# Sheet-BATTERY-V2_1.net
KiCad netlist of a schematic drawn in Altium Designer
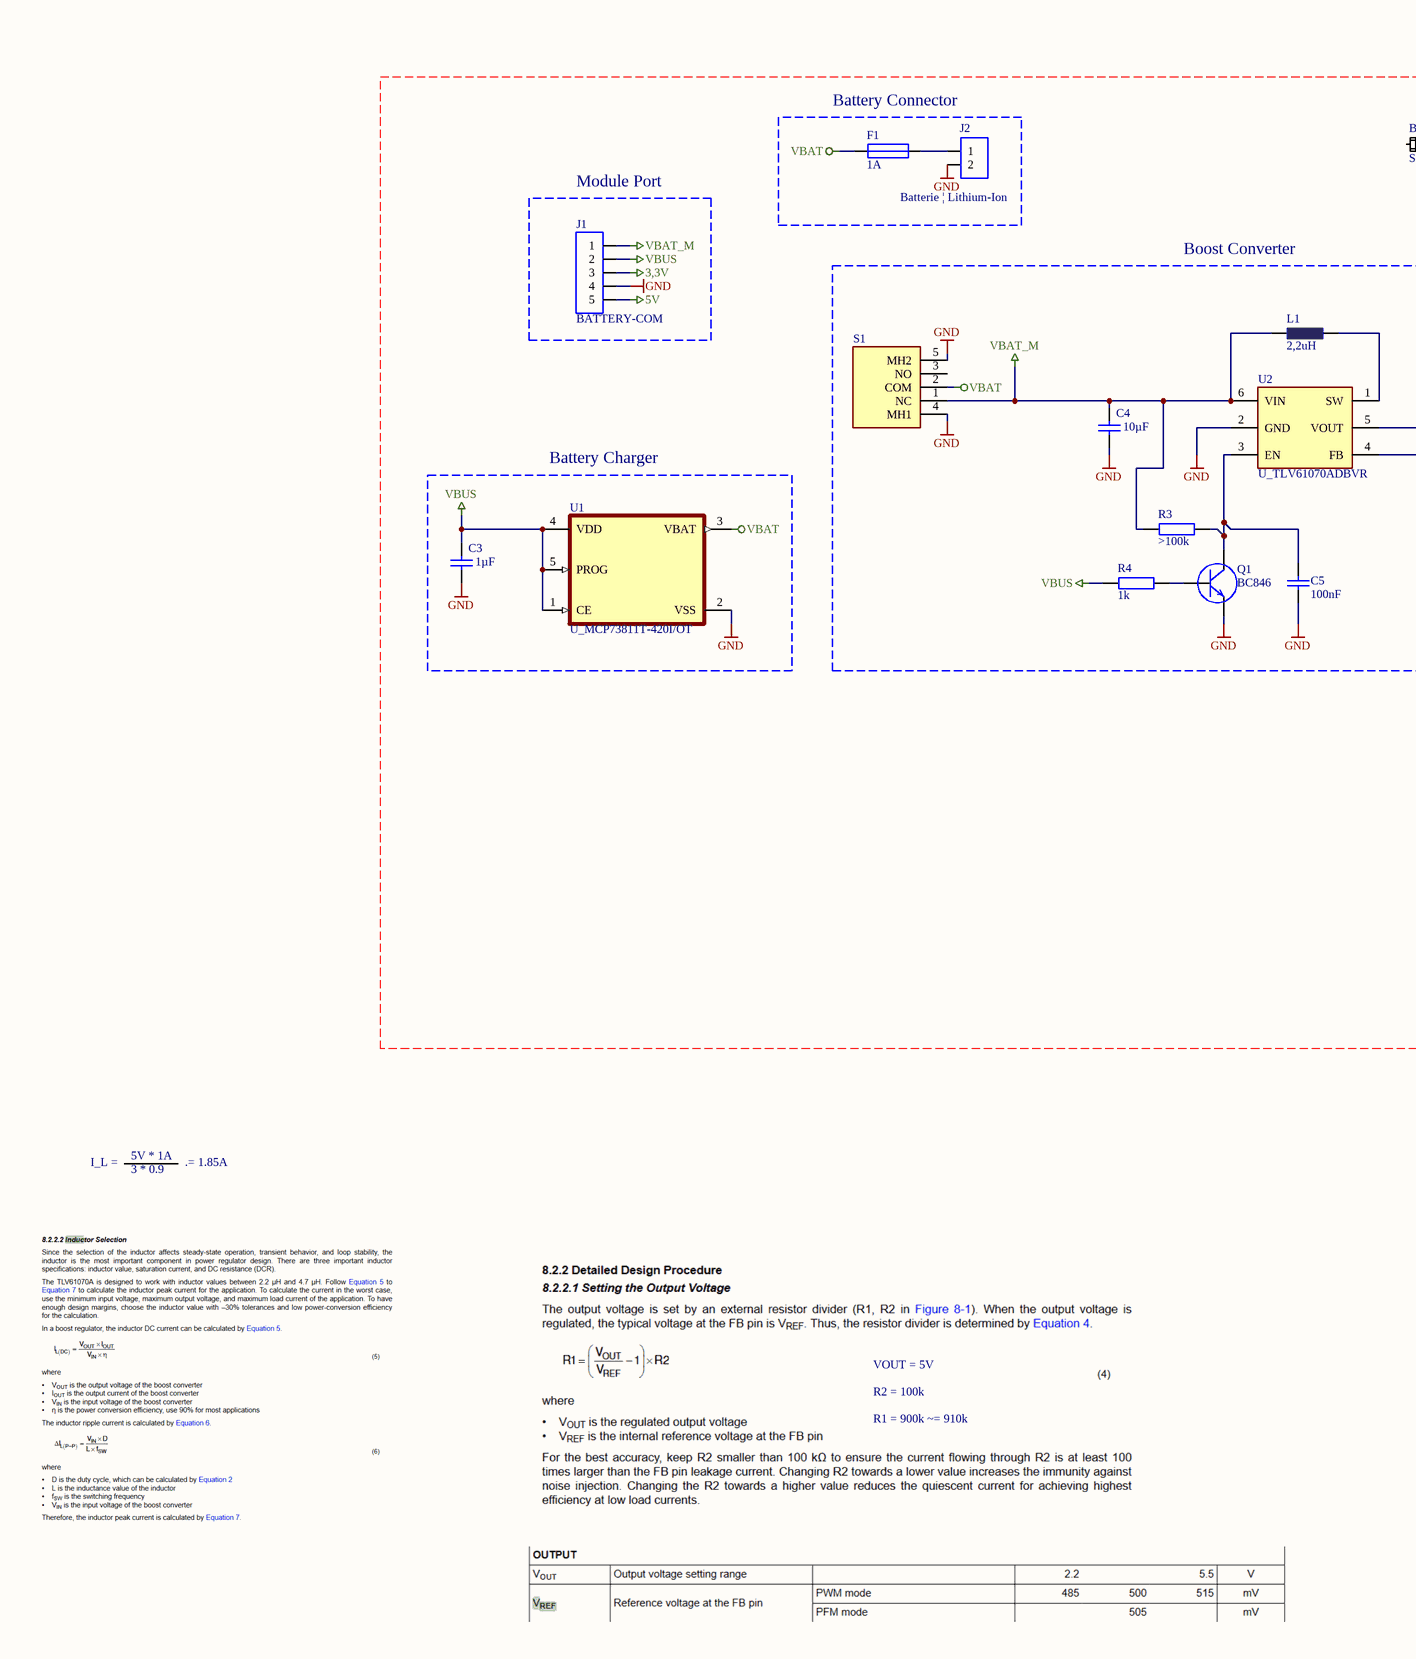
[diagram p0: Sheet-BATTERY-V2.1.SchDoc, left]
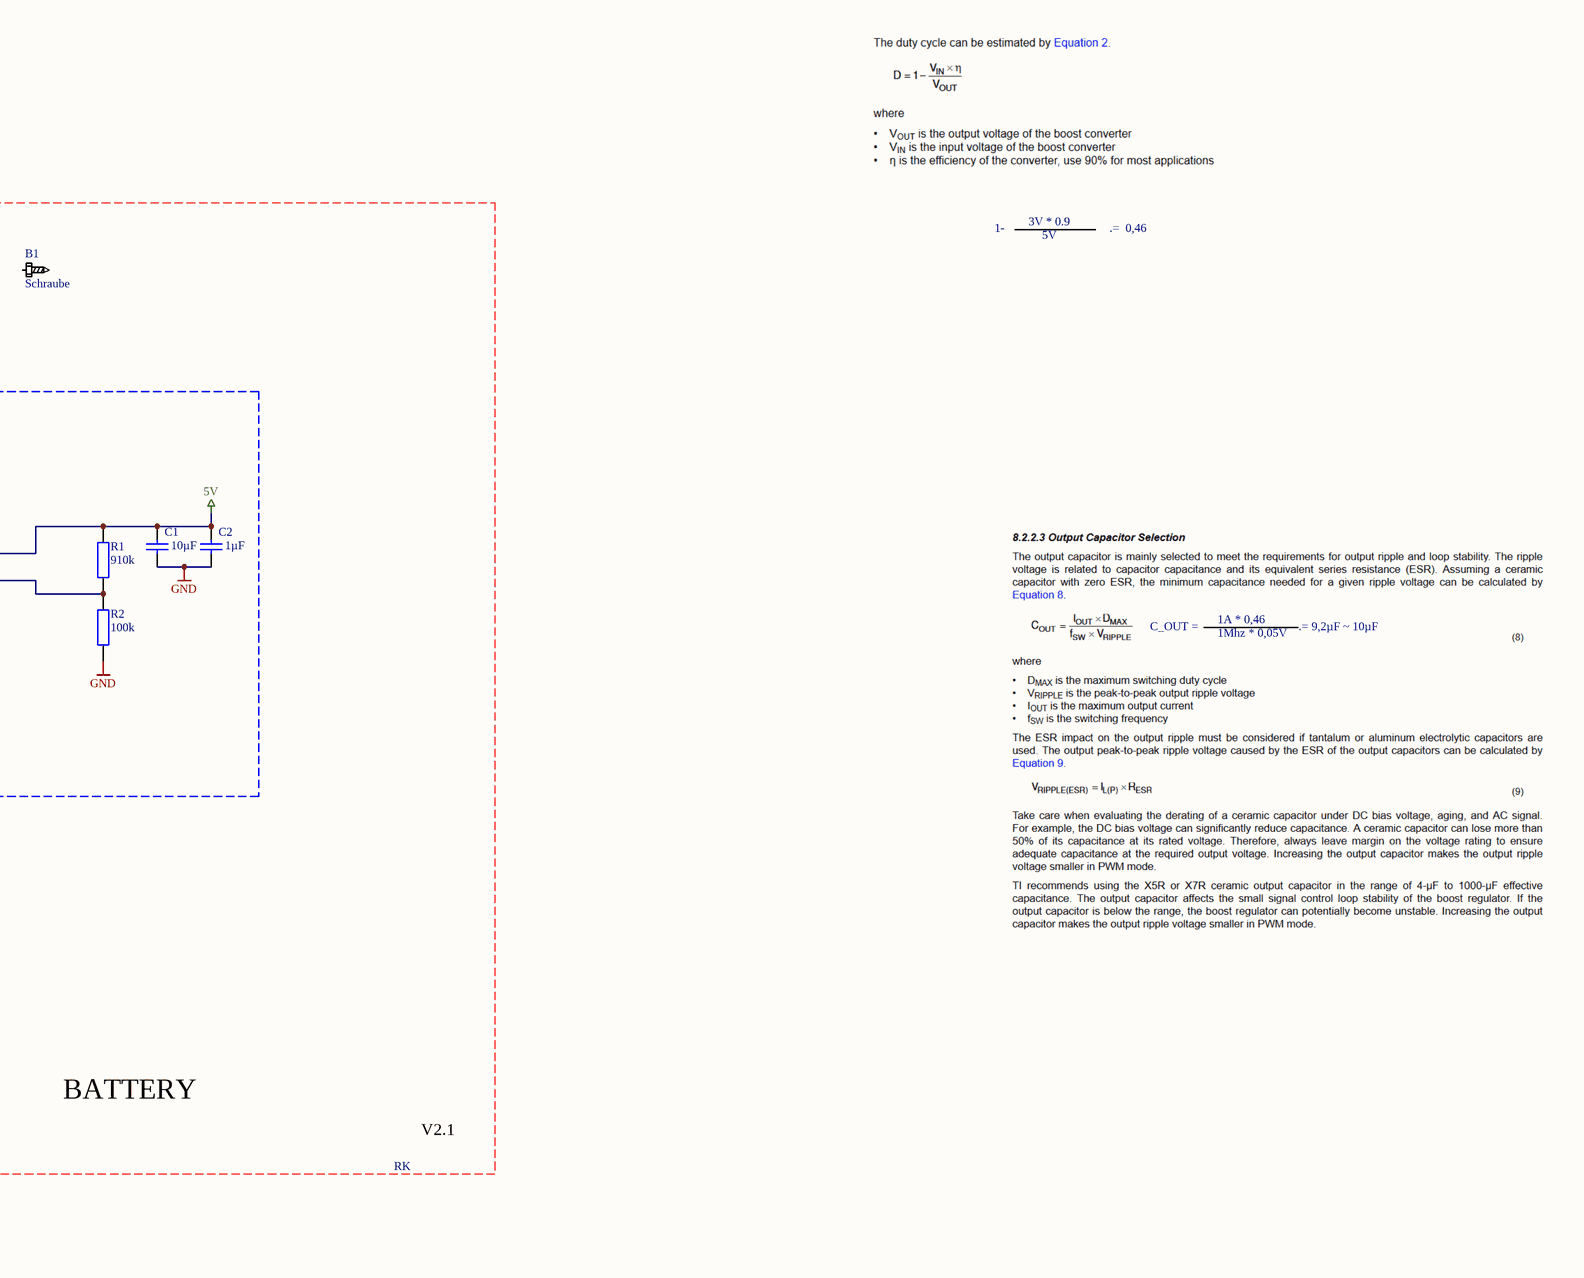
[diagram p1: Sheet-BATTERY-V2.1.SchDoc, right]

(export (version "E")
  (design (tool "Eeschema 10.0.6"))
  (components
    (comp (ref "B1")
      (value "Schraube")
      (footprint "B_Schraube-M3 PAD")
      (description "Schraubenloch für M3 Schrauben")
      (libsource (lib "SCHLIB-PCSB_5.1.3") (part "B_Schraube"))
    )
    (comp (ref "C1")
      (value "10µF")
      (footprint "C_SMD_0805")
      (description "Kondensator SMD Universal, Keramik, Folie, usw.")
      (libsource (lib "SCHLIB-PCSB_5.1.3") (part "C_SMD_KO"))
    )
    (comp (ref "C2")
      (value "1µF")
      (footprint "C_SMD_0603")
      (description "Kondensator SMD Universal, Keramik, Folie, usw.")
      (libsource (lib "SCHLIB-PCSB_5.1.3") (part "C_SMD_KO"))
    )
    (comp (ref "C3")
      (value "1µF")
      (footprint "C_SMD_0603")
      (description "Kondensator SMD Universal, Keramik, Folie, usw.")
      (libsource (lib "SCHLIB-PCSB_5.1.3") (part "C_SMD_KO"))
    )
    (comp (ref "C4")
      (value "10µF")
      (footprint "C_SMD_0805")
      (description "Kondensator SMD Universal, Keramik, Folie, usw.")
      (libsource (lib "SCHLIB-PCSB_5.1.3") (part "C_SMD_KO"))
    )
    (comp (ref "C5")
      (value "100nF")
      (footprint "C_SMD_0603")
      (description "Kondensator SMD Universal, Keramik, Folie, usw.")
      (libsource (lib "SCHLIB-PCSB_5.1.3") (part "C_SMD_KO"))
    )
    (comp (ref "F1")
      (value "1A")
      (footprint "F_OMF63_Schurtner")
      (description "Sicherung")
      (libsource (lib "SCHLIB-PCSB_5.1.3") (part "F_THT_Fuse"))
    )
    (comp (ref "J1")
      (value "BATTERY-COM")
      (footprint "SIP-5")
      (description "Stecker")
      (libsource (lib "SCHLIB-PCSB_5.1.3") (part "J_THT_CON5"))
    )
    (comp (ref "J2")
      (value "Batterie ¦ Lithium-Ion")
      (footprint "J_THT_Printklemme 2x")
      (description "Stecker")
      (libsource (lib "SCHLIB-PCSB_5.1.3") (part "J_THT_CON2"))
    )
    (comp (ref "L1")
      (value "2,2uH")
      (footprint "L_SMD_74438357100")
      (description "Spule SMD")
      (libsource (lib "SCHLIB-PCSB_5.1.3") (part "L_SMD_Spule"))
    )
    (comp (ref "Q1")
      (value "BC846")
      (footprint "SOT-23-3_BC846")
      (description "NPN Transistor")
      (libsource (lib "SCHLIB-PCSB_5.1.3") (part "Q_SMD_NPN"))
    )
    (comp (ref "R1")
      (value "910k")
      (footprint "R_SMD_0805")
      (description "Widerstand SMD")
      (libsource (lib "SCHLIB-PCSB_5.1.3") (part "R_SMD_Widerstand"))
    )
    (comp (ref "R2")
      (value "100k")
      (footprint "R_SMD_0805")
      (description "Widerstand SMD")
      (libsource (lib "SCHLIB-PCSB_5.1.3") (part "R_SMD_Widerstand"))
    )
    (comp (ref "R3")
      (value ">100k")
      (footprint "R_SMD_0603")
      (description "Widerstand SMD")
      (libsource (lib "SCHLIB-PCSB_5.1.3") (part "R_SMD_Widerstand"))
    )
    (comp (ref "R4")
      (value "1k")
      (footprint "R_SMD_0603")
      (description "Widerstand SMD")
      (libsource (lib "SCHLIB-PCSB_5.1.3") (part "R_SMD_Widerstand"))
    )
    (comp (ref "S1")
      (value "S_SLW-1298856-5A-RA-N-D")
      (footprint "SLW12988565ARAND")
      (description "Switch")
      (fields (field (name "MANUFACTURER_PART_NUMBER") "SLW-1298856-5A-RA-N-D"))
      (libsource (lib "SCHLIB-PCSB_5.1.3") (part "S_SLW-1298856-5A-RA-N-D"))
    )
    (comp (ref "U1")
      (value "U_MCP73811T-420I/OT")
      (footprint "SOT95P280X145-5N")
      (description "Charger IC Lithium Ion/Polymer SOT-23-5")
      (fields (field (name "MF") "Microchip") (field (name "MP") "MCP73811T-420I/OT"))
      (libsource (lib "SCHLIB-PCSB_5.1.3") (part "U_MCP73811T-420I/OT"))
    )
    (comp (ref "U2")
      (value "U_TLV61070ADBVR")
      (footprint "SOT23-6")
      (description "Integrated Circuit, Boost converter: Input 0.5 - 5.5V \r\nOutput 2.2 - 5.5V")
      (fields
        (field (name "MANUFACTURER_PART_NUMBER") "TLV61070ADBVR")
        (field (name "MOUSER PART NUMBER") "595-TLV61070ADBVR")
      )
      (libsource (lib "SCHLIB-PCSB_5.1.3") (part "U_TLV61070ADBVR"))
    )
  )
  (nets
    (net (code "1") (name "3,3V") (class "Default")
      (node (ref "J1") (pin "3") (pinfunction "3_3") (pintype "passive"))
    )
    (net (code "2") (name "5V") (class "Default")
      (node (ref "C1") (pin "1") (pintype "passive"))
      (node (ref "C2") (pin "1") (pintype "passive"))
      (node (ref "J1") (pin "5") (pinfunction "5_5") (pintype "passive"))
      (node (ref "R1") (pin "2") (pintype "passive"))
      (node (ref "U2") (pin "5") (pinfunction "VOUT_5") (pintype "passive"))
    )
    (net (code "3") (name "GND") (class "Default")
      (node (ref "C1") (pin "2") (pintype "passive"))
      (node (ref "C2") (pin "2") (pintype "passive"))
      (node (ref "C3") (pin "2") (pintype "passive"))
      (node (ref "C4") (pin "2") (pintype "passive"))
      (node (ref "C5") (pin "2") (pintype "passive"))
      (node (ref "J1") (pin "4") (pinfunction "4_4") (pintype "passive"))
      (node (ref "J2") (pin "2") (pinfunction "2_2") (pintype "passive"))
      (node (ref "Q1") (pin "E") (pinfunction "E_E") (pintype "passive"))
      (node (ref "R2") (pin "1") (pintype "passive"))
      (node (ref "S1") (pin "4") (pinfunction "MH1_4") (pintype "passive"))
      (node (ref "S1") (pin "5") (pinfunction "MH2_5") (pintype "passive"))
      (node (ref "U1") (pin "2") (pinfunction "VSS_2") (pintype "power_in"))
      (node (ref "U2") (pin "2") (pinfunction "GND_2") (pintype "passive"))
    )
    (net (code "4") (name "Net-(F1-Pad2)") (class "Default")
      (node (ref "F1") (pin "2") (pinfunction "2_2") (pintype "passive"))
      (node (ref "J2") (pin "1") (pinfunction "1_1") (pintype "passive"))
    )
    (net (code "5") (name "Net-(Q1-PadB)") (class "Default")
      (node (ref "Q1") (pin "B") (pinfunction "B_B") (pintype "passive"))
      (node (ref "R4") (pin "2") (pintype "passive"))
    )
    (net (code "6") (name "Net-(U2-EN)") (class "Default")
      (node (ref "C5") (pin "1") (pintype "passive"))
      (node (ref "Q1") (pin "C") (pinfunction "C_C") (pintype "passive"))
      (node (ref "R3") (pin "2") (pintype "passive"))
      (node (ref "U2") (pin "3") (pinfunction "EN_3") (pintype "passive"))
    )
    (net (code "7") (name "Net-(U2-FB)") (class "Default")
      (node (ref "R1") (pin "1") (pintype "passive"))
      (node (ref "R2") (pin "2") (pintype "passive"))
      (node (ref "U2") (pin "4") (pinfunction "FB_4") (pintype "passive"))
    )
    (net (code "8") (name "Net-(U2-SW)") (class "Default")
      (node (ref "L1") (pin "1") (pintype "passive"))
      (node (ref "U2") (pin "1") (pinfunction "SW_1") (pintype "passive"))
    )
    (net (code "9") (name "VBAT") (class "Default")
      (node (ref "F1") (pin "1") (pintype "passive"))
      (node (ref "S1") (pin "2") (pinfunction "COM_2") (pintype "passive"))
      (node (ref "U1") (pin "3") (pinfunction "VBAT_3") (pintype "output"))
    )
    (net (code "10") (name "VBAT_M") (class "Default")
      (node (ref "C4") (pin "1") (pintype "passive"))
      (node (ref "J1") (pin "1") (pinfunction "1_1") (pintype "passive"))
      (node (ref "L1") (pin "2") (pintype "passive"))
      (node (ref "R3") (pin "1") (pintype "passive"))
      (node (ref "S1") (pin "1") (pinfunction "NC_1") (pintype "passive"))
      (node (ref "U2") (pin "6") (pinfunction "VIN_6") (pintype "passive"))
    )
    (net (code "11") (name "VBUS") (class "Default")
      (node (ref "C3") (pin "1") (pintype "passive"))
      (node (ref "J1") (pin "2") (pinfunction "2_2") (pintype "passive"))
      (node (ref "R4") (pin "1") (pintype "passive"))
      (node (ref "U1") (pin "1") (pinfunction "CE_1") (pintype "input"))
      (node (ref "U1") (pin "4") (pinfunction "VDD_4") (pintype "power_in"))
      (node (ref "U1") (pin "5") (pinfunction "PROG_5") (pintype "input"))
    )
    (net (code "12") (name "unconnected-(B1-PAD-Pad1)") (class "Default")
      (node (ref "B1") (pin "1") (pinfunction "PAD_1") (pintype "passive"))
    )
    (net (code "13") (name "unconnected-(S1-NO-Pad3)") (class "Default")
      (node (ref "S1") (pin "3") (pinfunction "NO_3") (pintype "passive"))
    )
  )
)
